# ProProject_MSPM0L1306__2024-08-03.net
KiCad netlist of a schematic drawn in EasyEDA Pro
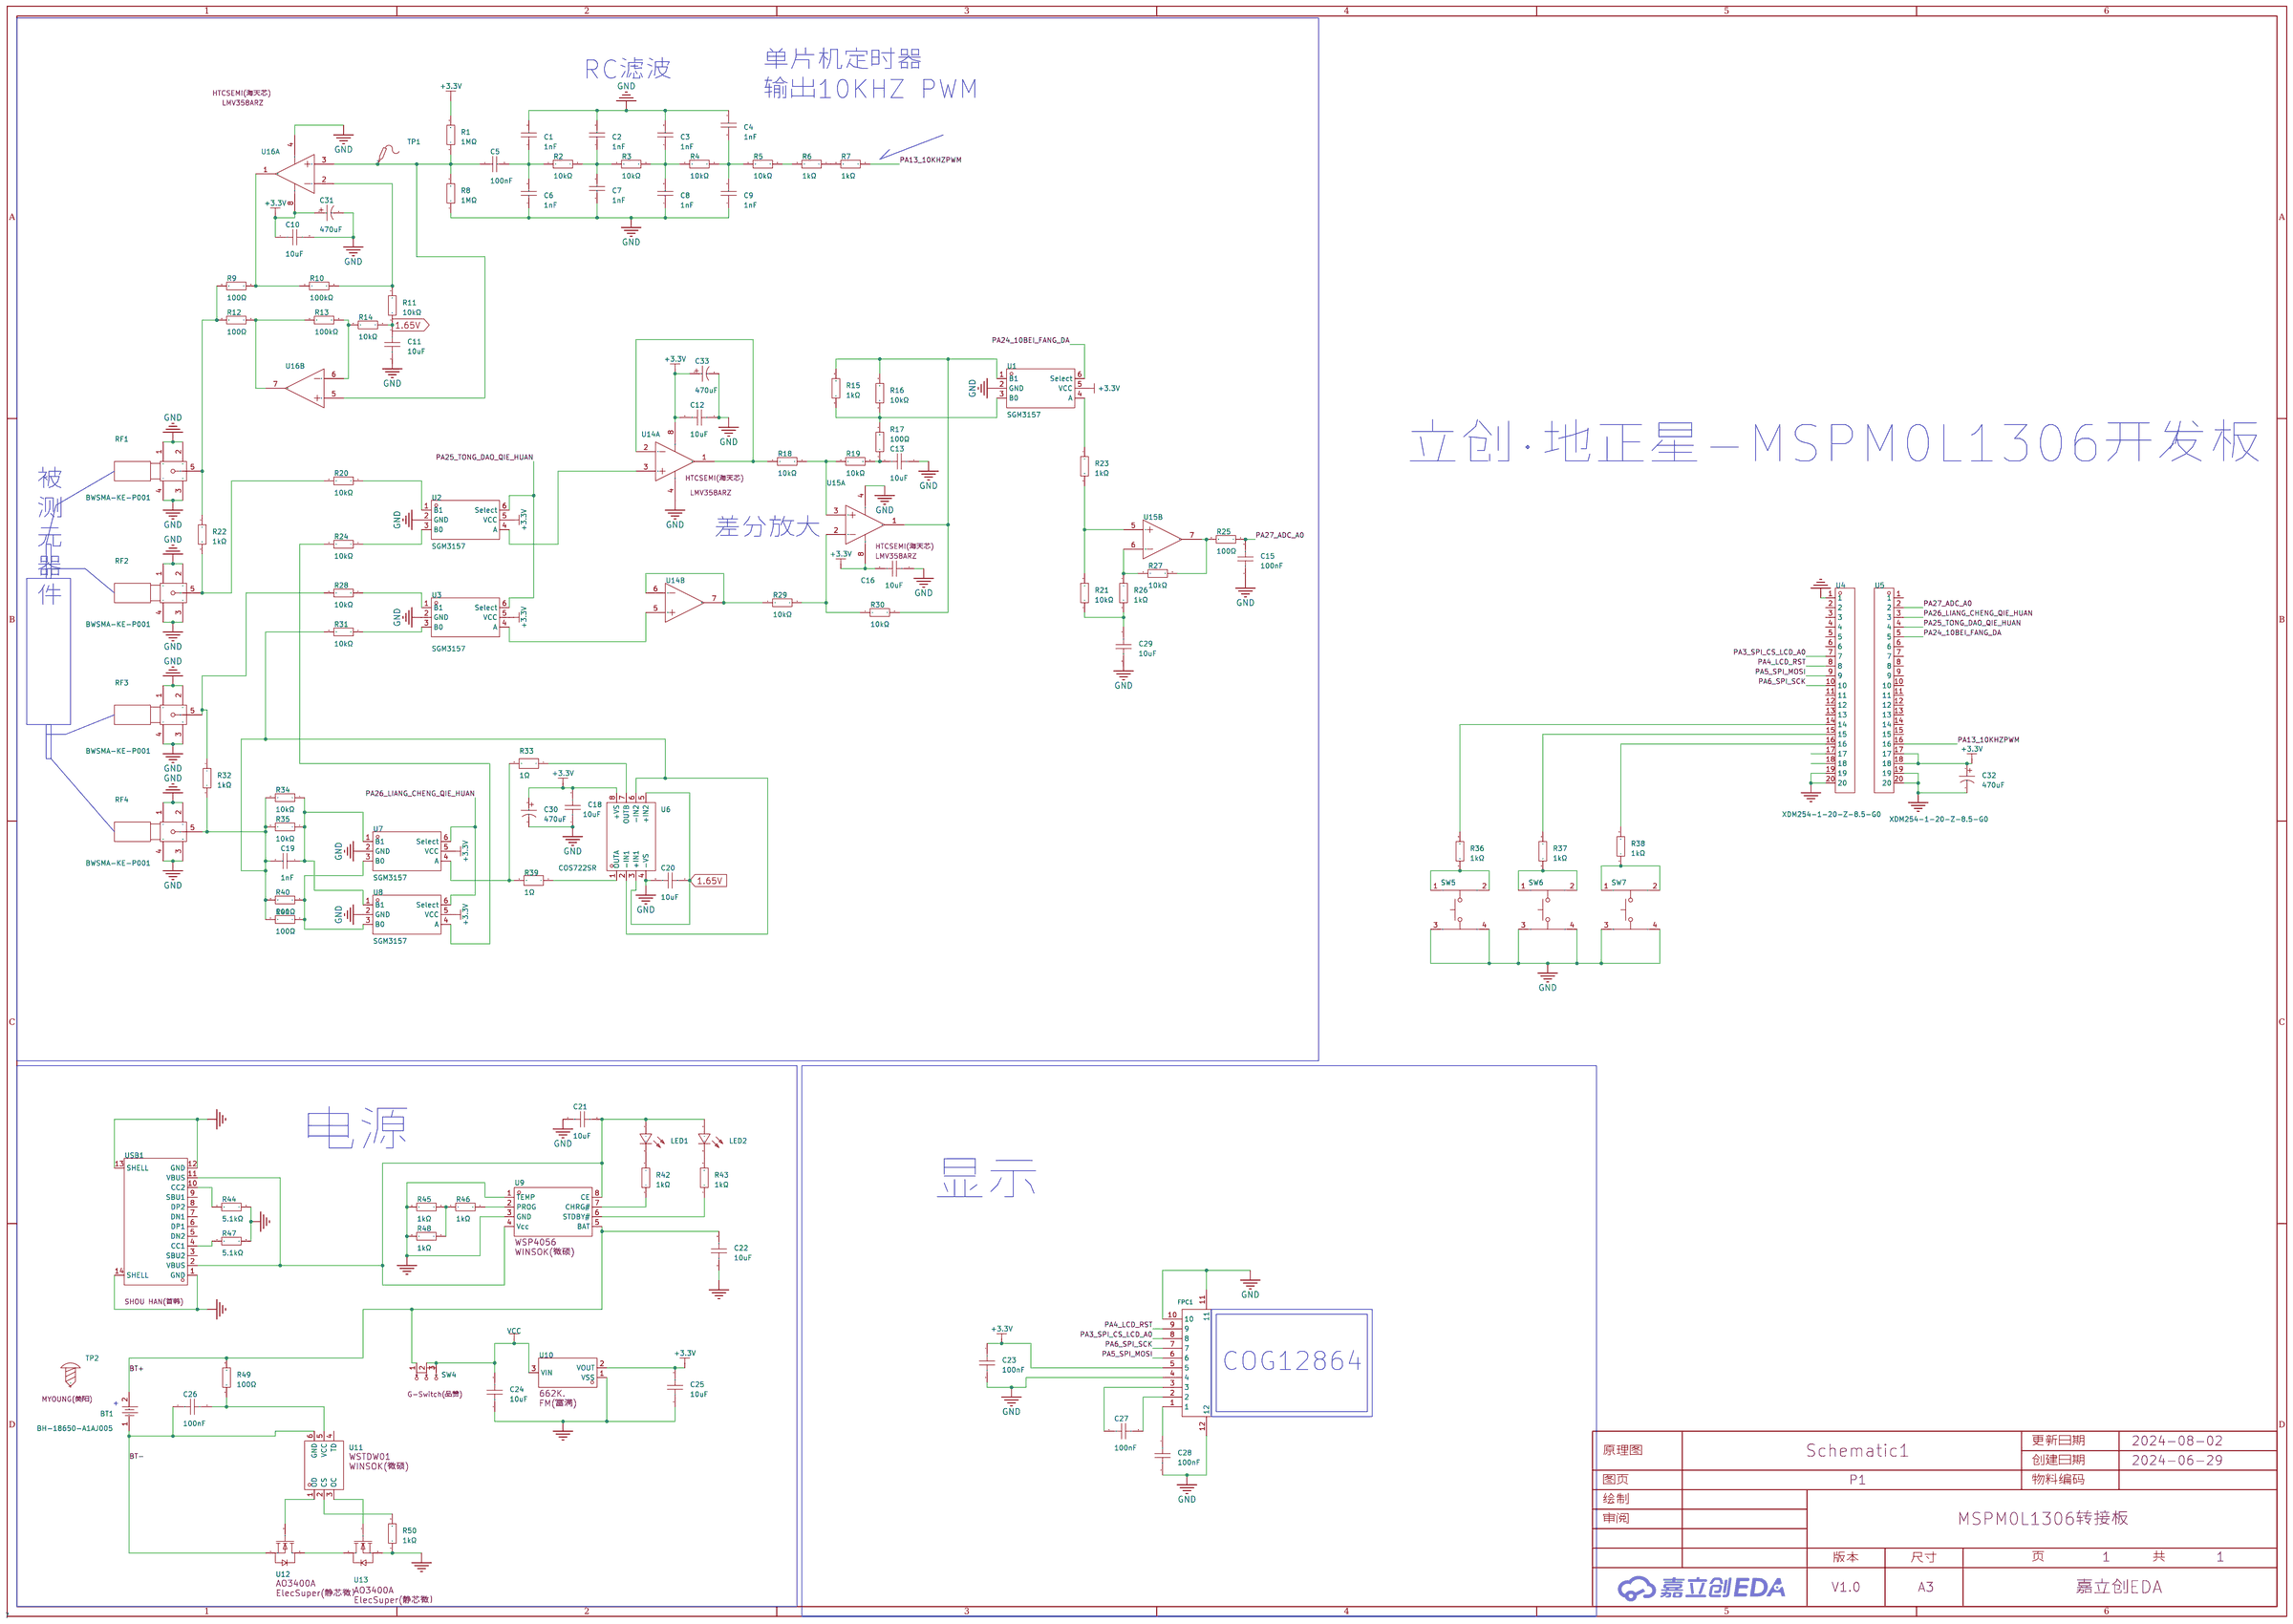
[diagram p0: schematic sheet]

(export (version "E")
  (design (tool "Eeschema 10.0.6"))
  (components
    (comp (ref "BT1")
      (value "BH-18650-A1AJ005")
      (footprint "easyedapro:BAT-TH_BH-18650-A1AJ005")
      (description "连接器类型:电池盒;适用电池规格:CR18650;触点电镀:镍;工作温度范围:-10°C~+100°C;")
      (fields (field (name "Manufacturer") "MYOUNG(美阳)"))
      (libsource (lib "easyedapro") (part "BH-18650-A1AJ005"))
    )
    (comp (ref "C1")
      (value "1nF")
      (footprint "easyedapro:C0603")
      (description "容值:1nF;精度:±5%;额定电压:50V;材质(温度系数):NP0;")
      (fields
        (field (name "Manufacturer Part") "CC0603JRNPO9BN102")
        (field (name "Manufacturer") "YAGEO(国巨)")
      )
      (libsource (lib "easyedapro") (part "CC0603JRNPO9BN102"))
    )
    (comp (ref "C2")
      (value "1nF")
      (footprint "easyedapro:C0603")
      (description "容值:1nF;精度:±5%;额定电压:50V;材质(温度系数):NP0;")
      (fields
        (field (name "Manufacturer Part") "CC0603JRNPO9BN102")
        (field (name "Manufacturer") "YAGEO(国巨)")
      )
      (libsource (lib "easyedapro") (part "CC0603JRNPO9BN102"))
    )
    (comp (ref "C3")
      (value "1nF")
      (footprint "easyedapro:C0603")
      (description "容值:1nF;精度:±5%;额定电压:50V;材质(温度系数):NP0;")
      (fields
        (field (name "Manufacturer Part") "CC0603JRNPO9BN102")
        (field (name "Manufacturer") "YAGEO(国巨)")
      )
      (libsource (lib "easyedapro") (part "CC0603JRNPO9BN102"))
    )
    (comp (ref "C4")
      (value "1nF")
      (footprint "easyedapro:C0603")
      (description "容值:1nF;精度:±5%;额定电压:50V;材质(温度系数):NP0;")
      (fields
        (field (name "Manufacturer Part") "CC0603JRNPO9BN102")
        (field (name "Manufacturer") "YAGEO(国巨)")
      )
      (libsource (lib "easyedapro") (part "CC0603JRNPO9BN102"))
    )
    (comp (ref "C5")
      (value "100nF")
      (footprint "easyedapro:C0603")
      (description "容值:100nF;精度:±10%;额定电压:50V;材质(温度系数):X7R;")
      (fields (field (name "Manufacturer Part") "0603B104K500NT") (field (name "Manufacturer") "FH(风华)"))
      (libsource (lib "easyedapro") (part "0603B104K500NT"))
    )
    (comp (ref "C6")
      (value "1nF")
      (footprint "easyedapro:C0603")
      (description "容值:1nF;精度:±5%;额定电压:50V;材质(温度系数):NP0;")
      (fields
        (field (name "Manufacturer Part") "CC0603JRNPO9BN102")
        (field (name "Manufacturer") "YAGEO(国巨)")
      )
      (libsource (lib "easyedapro") (part "CC0603JRNPO9BN102"))
    )
    (comp (ref "C7")
      (value "1nF")
      (footprint "easyedapro:C0603")
      (description "容值:1nF;精度:±5%;额定电压:50V;材质(温度系数):NP0;")
      (fields
        (field (name "Manufacturer Part") "CC0603JRNPO9BN102")
        (field (name "Manufacturer") "YAGEO(国巨)")
      )
      (libsource (lib "easyedapro") (part "CC0603JRNPO9BN102"))
    )
    (comp (ref "C8")
      (value "1nF")
      (footprint "easyedapro:C0603")
      (description "容值:1nF;精度:±5%;额定电压:50V;材质(温度系数):NP0;")
      (fields
        (field (name "Manufacturer Part") "CC0603JRNPO9BN102")
        (field (name "Manufacturer") "YAGEO(国巨)")
      )
      (libsource (lib "easyedapro") (part "CC0603JRNPO9BN102"))
    )
    (comp (ref "C9")
      (value "1nF")
      (footprint "easyedapro:C0603")
      (description "容值:1nF;精度:±5%;额定电压:50V;材质(温度系数):NP0;")
      (fields
        (field (name "Manufacturer Part") "CC0603JRNPO9BN102")
        (field (name "Manufacturer") "YAGEO(国巨)")
      )
      (libsource (lib "easyedapro") (part "CC0603JRNPO9BN102"))
    )
    (comp (ref "C10")
      (value "10uF")
      (footprint "easyedapro:C0603")
      (description "容值:10uF;精度:±10%;额定电压:10V;材质(温度系数):X5R;")
      (fields
        (field (name "Manufacturer Part") "CL10A106KP8NNNC")
        (field (name "Manufacturer") "SAMSUNG(三星)")
      )
      (libsource (lib "easyedapro") (part "CL10A106KP8NNNC"))
    )
    (comp (ref "C11")
      (value "10uF")
      (footprint "easyedapro:C0603")
      (description "容值:10uF;精度:±10%;额定电压:10V;材质(温度系数):X5R;")
      (fields
        (field (name "Manufacturer Part") "CL10A106KP8NNNC")
        (field (name "Manufacturer") "SAMSUNG(三星)")
      )
      (libsource (lib "easyedapro") (part "CL10A106KP8NNNC"))
    )
    (comp (ref "C12")
      (value "10uF")
      (footprint "easyedapro:C0603")
      (description "容值:10uF;精度:±10%;额定电压:10V;材质(温度系数):X5R;")
      (fields
        (field (name "Manufacturer Part") "CL10A106KP8NNNC")
        (field (name "Manufacturer") "SAMSUNG(三星)")
      )
      (libsource (lib "easyedapro") (part "CL10A106KP8NNNC"))
    )
    (comp (ref "C13")
      (value "10uF")
      (footprint "easyedapro:C0603")
      (description "容值:10uF;精度:±10%;额定电压:10V;材质(温度系数):X5R;")
      (fields
        (field (name "Manufacturer Part") "CL10A106KP8NNNC")
        (field (name "Manufacturer") "SAMSUNG(三星)")
      )
      (libsource (lib "easyedapro") (part "CL10A106KP8NNNC"))
    )
    (comp (ref "C15")
      (value "100nF")
      (footprint "easyedapro:C0603")
      (description "容值:100nF;精度:±10%;额定电压:50V;材质(温度系数):X7R;")
      (fields
        (field (name "Manufacturer Part") "CC0603KRX7R9BB104")
        (field (name "Manufacturer") "YAGEO(国巨)")
      )
      (libsource (lib "easyedapro") (part "CC0603KRX7R9BB104"))
    )
    (comp (ref "C16")
      (value "10uF")
      (footprint "easyedapro:C0603")
      (description "容值:10uF;精度:±10%;额定电压:10V;材质(温度系数):X5R;")
      (fields
        (field (name "Manufacturer Part") "CL10A106KP8NNNC")
        (field (name "Manufacturer") "SAMSUNG(三星)")
      )
      (libsource (lib "easyedapro") (part "CL10A106KP8NNNC"))
    )
    (comp (ref "C18")
      (value "10uF")
      (footprint "easyedapro:C0603")
      (description "容值:10uF;精度:±10%;额定电压:10V;材质(温度系数):X5R;")
      (fields
        (field (name "Manufacturer Part") "CL10A106KP8NNNC")
        (field (name "Manufacturer") "SAMSUNG(三星)")
      )
      (libsource (lib "easyedapro") (part "CL10A106KP8NNNC"))
    )
    (comp (ref "C19")
      (value "1nF")
      (footprint "easyedapro:C0603")
      (description "容值:1nF;精度:±5%;额定电压:50V;材质(温度系数):NP0;")
      (fields
        (field (name "Manufacturer Part") "CC0603JRNPO9BN102")
        (field (name "Manufacturer") "YAGEO(国巨)")
      )
      (libsource (lib "easyedapro") (part "CC0603JRNPO9BN102"))
    )
    (comp (ref "C20")
      (value "10uF")
      (footprint "easyedapro:C0603")
      (description "容值:10uF;精度:±10%;额定电压:10V;材质(温度系数):X5R;")
      (fields
        (field (name "Manufacturer Part") "CL10A106KP8NNNC")
        (field (name "Manufacturer") "SAMSUNG(三星)")
      )
      (libsource (lib "easyedapro") (part "CL10A106KP8NNNC"))
    )
    (comp (ref "C21")
      (value "10uF")
      (footprint "easyedapro:C0603")
      (description "容值:10uF;精度:±10%;额定电压:10V;材质(温度系数):X5R;")
      (fields
        (field (name "Manufacturer Part") "CL10A106KP8NNNC")
        (field (name "Manufacturer") "SAMSUNG(三星)")
      )
      (libsource (lib "easyedapro") (part "CL10A106KP8NNNC"))
    )
    (comp (ref "C22")
      (value "10uF")
      (footprint "easyedapro:C0603")
      (description "容值:10uF;精度:±10%;额定电压:10V;材质(温度系数):X5R;")
      (fields
        (field (name "Manufacturer Part") "CL10A106KP8NNNC")
        (field (name "Manufacturer") "SAMSUNG(三星)")
      )
      (libsource (lib "easyedapro") (part "CL10A106KP8NNNC"))
    )
    (comp (ref "C23")
      (value "100nF")
      (footprint "easyedapro:C0603")
      (description "容值:100nF;精度:±10%;额定电压:50V;材质(温度系数):X7R;")
      (fields
        (field (name "Manufacturer Part") "CC0603KRX7R9BB104")
        (field (name "Manufacturer") "YAGEO(国巨)")
      )
      (libsource (lib "easyedapro") (part "CC0603KRX7R9BB104"))
    )
    (comp (ref "C24")
      (value "10uF")
      (footprint "easyedapro:C0603")
      (description "容值:10uF;精度:±10%;额定电压:10V;材质(温度系数):X5R;")
      (fields
        (field (name "Manufacturer Part") "CL10A106KP8NNNC")
        (field (name "Manufacturer") "SAMSUNG(三星)")
      )
      (libsource (lib "easyedapro") (part "CL10A106KP8NNNC"))
    )
    (comp (ref "C25")
      (value "10uF")
      (footprint "easyedapro:C0603")
      (description "容值:10uF;精度:±10%;额定电压:10V;材质(温度系数):X5R;")
      (fields
        (field (name "Manufacturer Part") "CL10A106KP8NNNC")
        (field (name "Manufacturer") "SAMSUNG(三星)")
      )
      (libsource (lib "easyedapro") (part "CL10A106KP8NNNC"))
    )
    (comp (ref "C26")
      (value "100nF")
      (footprint "easyedapro:C0603")
      (description "容值:100nF;精度:±10%;额定电压:50V;材质(温度系数):X7R;")
      (fields
        (field (name "Manufacturer Part") "CC0603KRX7R9BB104")
        (field (name "Manufacturer") "YAGEO(国巨)")
      )
      (libsource (lib "easyedapro") (part "CC0603KRX7R9BB104"))
    )
    (comp (ref "C27")
      (value "100nF")
      (footprint "easyedapro:C0603")
      (description "容值:100nF;精度:±10%;额定电压:50V;材质(温度系数):X7R;")
      (fields
        (field (name "Manufacturer Part") "CC0603KRX7R9BB104")
        (field (name "Manufacturer") "YAGEO(国巨)")
      )
      (libsource (lib "easyedapro") (part "CC0603KRX7R9BB104"))
    )
    (comp (ref "C28")
      (value "100nF")
      (footprint "easyedapro:C0603")
      (description "容值:100nF;精度:±10%;额定电压:50V;材质(温度系数):X7R;")
      (fields
        (field (name "Manufacturer Part") "CC0603KRX7R9BB104")
        (field (name "Manufacturer") "YAGEO(国巨)")
      )
      (libsource (lib "easyedapro") (part "CC0603KRX7R9BB104"))
    )
    (comp (ref "C29")
      (value "10uF")
      (footprint "easyedapro:C0603")
      (description "容值:10uF;精度:±10%;额定电压:10V;材质(温度系数):X5R;")
      (fields
        (field (name "Manufacturer Part") "CL10A106KP8NNNC")
        (field (name "Manufacturer") "SAMSUNG(三星)")
      )
      (libsource (lib "easyedapro") (part "CL10A106KP8NNNC"))
    )
    (comp (ref "C30")
      (value "470uF")
      (footprint "easyedapro:CAP-TH_BD8.0-P3.50-D0.6-FD")
      (description "容值:470uF;精度:±20%;额定电压:16V;")
      (fields
        (field (name "Manufacturer Part") "KM477M016F12RR0VH2FP0")
        (field (name "Manufacturer") "CX(承兴)")
      )
      (libsource (lib "easyedapro") (part "470uf16v"))
    )
    (comp (ref "C31")
      (value "470uF")
      (footprint "easyedapro:CAP-TH_BD8.0-P3.50-D0.6-FD")
      (description "容值:470uF;精度:±20%;额定电压:16V;")
      (fields
        (field (name "Manufacturer Part") "KM477M016F12RR0VH2FP0")
        (field (name "Manufacturer") "CX(承兴)")
      )
      (libsource (lib "easyedapro") (part "470uf16v"))
    )
    (comp (ref "C32")
      (value "470uF")
      (footprint "easyedapro:CAP-TH_BD8.0-P3.50-D0.6-FD")
      (description "容值:470uF;精度:±20%;额定电压:16V;")
      (fields
        (field (name "Manufacturer Part") "KM477M016F12RR0VH2FP0")
        (field (name "Manufacturer") "CX(承兴)")
      )
      (libsource (lib "easyedapro") (part "470uf16v"))
    )
    (comp (ref "C33")
      (value "470uF")
      (footprint "easyedapro:CAP-TH_BD8.0-P3.50-D0.6-FD")
      (description "容值:470uF;精度:±20%;额定电压:16V;")
      (fields
        (field (name "Manufacturer Part") "KM477M016F12RR0VH2FP0")
        (field (name "Manufacturer") "CX(承兴)")
      )
      (libsource (lib "easyedapro") (part "470uf16v"))
    )
    (comp (ref "FPC1")
      (value "{ManufacturerPart!}")
      (footprint "easyedapro:FPC-SMD_10P-P1.0_FGS-XJ-H2.0")
      (description "间距:1mm;触点数量:10;锁定特性:翻盖式;安装类型:卧贴;触点类型:下接;")
      (fields (field (name "Manufacturer Part") "AFA01-S10FCA-00") (field (name "Manufacturer") "JS(钜硕电子)"))
      (libsource (lib "easyedapro") (part "AFA01-S10FCA-00"))
    )
    (comp (ref "LED1")
      (value "204-10SURD/S530-A3-L")
      (footprint "easyedapro:LED-TH_BD3.0-P2.54-FD")
      (description "发光颜色:红灯;二极管配置:-;主波长:624nm;色温:-;功率:60mW;安装方式:-;")
      (fields (field (name "Manufacturer") "EVERLIGHT(亿光)"))
      (libsource (lib "easyedapro") (part "204-10SURD/S530-A3-L"))
    )
    (comp (ref "LED2")
      (value "204-10SURD/S530-A3-L")
      (footprint "easyedapro:LED-TH_BD3.0-P2.54-FD")
      (description "发光颜色:红灯;二极管配置:-;主波长:624nm;色温:-;功率:60mW;安装方式:-;")
      (fields (field (name "Manufacturer") "EVERLIGHT(亿光)"))
      (libsource (lib "easyedapro") (part "204-10SURD/S530-A3-L"))
    )
    (comp (ref "R1")
      (value "1MΩ")
      (footprint "easyedapro:R0603")
      (description "电阻类型:厚膜电阻;阻值:1MΩ;精度:±1%;功率:100mW;")
      (fields
        (field (name "Manufacturer Part") "0603WAF1004T5E")
        (field (name "Manufacturer") "UNI-ROYAL(厚声)")
      )
      (libsource (lib "easyedapro") (part "0603WAF1004T5E"))
    )
    (comp (ref "R2")
      (value "10kΩ")
      (footprint "easyedapro:R0603")
      (description "电阻类型:厚膜电阻;阻值:10kΩ;精度:±1%;功率:100mW;")
      (fields (field (name "Manufacturer Part") "RC0603FR-0710KL") (field (name "Manufacturer") "YAGEO(国巨)"))
      (libsource (lib "easyedapro") (part "RC0603FR-0710KL"))
    )
    (comp (ref "R3")
      (value "10kΩ")
      (footprint "easyedapro:R0603")
      (description "电阻类型:厚膜电阻;阻值:10kΩ;精度:±1%;功率:100mW;")
      (fields (field (name "Manufacturer Part") "RC0603FR-0710KL") (field (name "Manufacturer") "YAGEO(国巨)"))
      (libsource (lib "easyedapro") (part "RC0603FR-0710KL"))
    )
    (comp (ref "R4")
      (value "10kΩ")
      (footprint "easyedapro:R0603")
      (description "电阻类型:厚膜电阻;阻值:10kΩ;精度:±1%;功率:100mW;")
      (fields (field (name "Manufacturer Part") "RC0603FR-0710KL") (field (name "Manufacturer") "YAGEO(国巨)"))
      (libsource (lib "easyedapro") (part "RC0603FR-0710KL"))
    )
    (comp (ref "R5")
      (value "10kΩ")
      (footprint "easyedapro:R0603")
      (description "电阻类型:厚膜电阻;阻值:10kΩ;精度:±1%;功率:100mW;")
      (fields (field (name "Manufacturer Part") "RC0603FR-0710KL") (field (name "Manufacturer") "YAGEO(国巨)"))
      (libsource (lib "easyedapro") (part "RC0603FR-0710KL"))
    )
    (comp (ref "R6")
      (value "1kΩ")
      (footprint "easyedapro:R0603")
      (description "电阻类型:厚膜电阻;阻值:1kΩ;精度:±1%;功率:100mW;")
      (fields (field (name "Manufacturer Part") "RC0603FR-071KL") (field (name "Manufacturer") "YAGEO(国巨)"))
      (libsource (lib "easyedapro") (part "RC0603FR-071KL"))
    )
    (comp (ref "R7")
      (value "1kΩ")
      (footprint "easyedapro:R0603")
      (description "电阻类型:厚膜电阻;阻值:1kΩ;精度:±1%;功率:100mW;")
      (fields (field (name "Manufacturer Part") "RC0603FR-071KL") (field (name "Manufacturer") "YAGEO(国巨)"))
      (libsource (lib "easyedapro") (part "RC0603FR-071KL"))
    )
    (comp (ref "R8")
      (value "1MΩ")
      (footprint "easyedapro:R0603")
      (description "电阻类型:厚膜电阻;阻值:1MΩ;精度:±1%;功率:100mW;")
      (fields
        (field (name "Manufacturer Part") "0603WAF1004T5E")
        (field (name "Manufacturer") "UNI-ROYAL(厚声)")
      )
      (libsource (lib "easyedapro") (part "0603WAF1004T5E"))
    )
    (comp (ref "R9")
      (value "100Ω")
      (footprint "easyedapro:R0603")
      (description "电阻类型:厚膜电阻;阻值:100Ω;精度:±1%;功率:100mW;")
      (fields (field (name "Manufacturer Part") "RC0603FR-07100RL") (field (name "Manufacturer") "YAGEO(国巨)"))
      (libsource (lib "easyedapro") (part "RC0603FR-07100RL"))
    )
    (comp (ref "R10")
      (value "100kΩ")
      (footprint "easyedapro:R0603")
      (description "电阻类型:厚膜电阻;阻值:100kΩ;精度:±1%;功率:100mW;")
      (fields (field (name "Manufacturer Part") "RC0603FR-07100KL") (field (name "Manufacturer") "YAGEO(国巨)"))
      (libsource (lib "easyedapro") (part "RC0603FR-07100KL"))
    )
    (comp (ref "R11")
      (value "10kΩ")
      (footprint "easyedapro:R0603")
      (description "电阻类型:厚膜电阻;阻值:10kΩ;精度:±1%;功率:100mW;")
      (fields (field (name "Manufacturer Part") "RC0603FR-0710KL") (field (name "Manufacturer") "YAGEO(国巨)"))
      (libsource (lib "easyedapro") (part "RC0603FR-0710KL"))
    )
    (comp (ref "R12")
      (value "100Ω")
      (footprint "easyedapro:R0603")
      (description "电阻类型:厚膜电阻;阻值:100Ω;精度:±1%;功率:100mW;")
      (fields (field (name "Manufacturer Part") "RC0603FR-07100RL") (field (name "Manufacturer") "YAGEO(国巨)"))
      (libsource (lib "easyedapro") (part "RC0603FR-07100RL"))
    )
    (comp (ref "R13")
      (value "100kΩ")
      (footprint "easyedapro:R0603")
      (description "电阻类型:厚膜电阻;阻值:100kΩ;精度:±1%;功率:100mW;")
      (fields (field (name "Manufacturer Part") "RC0603FR-07100KL") (field (name "Manufacturer") "YAGEO(国巨)"))
      (libsource (lib "easyedapro") (part "RC0603FR-07100KL"))
    )
    (comp (ref "R14")
      (value "10kΩ")
      (footprint "easyedapro:R0603")
      (description "电阻类型:厚膜电阻;阻值:10kΩ;精度:±1%;功率:100mW;")
      (fields (field (name "Manufacturer Part") "RC0603FR-0710KL") (field (name "Manufacturer") "YAGEO(国巨)"))
      (libsource (lib "easyedapro") (part "RC0603FR-0710KL"))
    )
    (comp (ref "R15")
      (value "1kΩ")
      (footprint "easyedapro:R0603")
      (description "电阻类型:厚膜电阻;阻值:1kΩ;精度:±1%;功率:100mW;")
      (fields (field (name "Manufacturer Part") "RC0603FR-071KL") (field (name "Manufacturer") "YAGEO(国巨)"))
      (libsource (lib "easyedapro") (part "RC0603FR-071KL"))
    )
    (comp (ref "R16")
      (value "10kΩ")
      (footprint "easyedapro:R0603")
      (description "电阻类型:厚膜电阻;阻值:10kΩ;精度:±1%;功率:100mW;")
      (fields (field (name "Manufacturer Part") "RC0603FR-0710KL") (field (name "Manufacturer") "YAGEO(国巨)"))
      (libsource (lib "easyedapro") (part "RC0603FR-0710KL"))
    )
    (comp (ref "R17")
      (value "100Ω")
      (footprint "easyedapro:R0603")
      (description "电阻类型:厚膜电阻;阻值:100Ω;精度:±1%;功率:100mW;")
      (fields (field (name "Manufacturer Part") "RC0603FR-07100RL") (field (name "Manufacturer") "YAGEO(国巨)"))
      (libsource (lib "easyedapro") (part "RC0603FR-07100RL"))
    )
    (comp (ref "R18")
      (value "10kΩ")
      (footprint "easyedapro:R0603")
      (description "电阻类型:厚膜电阻;阻值:10kΩ;精度:±1%;功率:100mW;")
      (fields (field (name "Manufacturer Part") "RC0603FR-0710KL") (field (name "Manufacturer") "YAGEO(国巨)"))
      (libsource (lib "easyedapro") (part "RC0603FR-0710KL"))
    )
    (comp (ref "R19")
      (value "10kΩ")
      (footprint "easyedapro:R0603")
      (description "电阻类型:厚膜电阻;阻值:10kΩ;精度:±1%;功率:100mW;")
      (fields (field (name "Manufacturer Part") "RC0603FR-0710KL") (field (name "Manufacturer") "YAGEO(国巨)"))
      (libsource (lib "easyedapro") (part "RC0603FR-0710KL"))
    )
    (comp (ref "R20")
      (value "10kΩ")
      (footprint "easyedapro:R0603")
      (description "电阻类型:厚膜电阻;阻值:10kΩ;精度:±1%;功率:100mW;")
      (fields (field (name "Manufacturer Part") "RC0603FR-0710KL") (field (name "Manufacturer") "YAGEO(国巨)"))
      (libsource (lib "easyedapro") (part "RC0603FR-0710KL"))
    )
    (comp (ref "R21")
      (value "10kΩ")
      (footprint "easyedapro:R0603")
      (description "电阻类型:厚膜电阻;阻值:10kΩ;精度:±1%;功率:100mW;")
      (fields (field (name "Manufacturer Part") "RC0603FR-0710KL") (field (name "Manufacturer") "YAGEO(国巨)"))
      (libsource (lib "easyedapro") (part "RC0603FR-0710KL"))
    )
    (comp (ref "R22")
      (value "1kΩ")
      (footprint "easyedapro:R0603")
      (description "电阻类型:厚膜电阻;阻值:1kΩ;精度:±1%;功率:100mW;")
      (fields (field (name "Manufacturer Part") "RC0603FR-071KL") (field (name "Manufacturer") "YAGEO(国巨)"))
      (libsource (lib "easyedapro") (part "RC0603FR-071KL"))
    )
    (comp (ref "R23")
      (value "1kΩ")
      (footprint "easyedapro:R0603")
      (description "电阻类型:厚膜电阻;阻值:1kΩ;精度:±1%;功率:100mW;")
      (fields (field (name "Manufacturer Part") "RC0603FR-071KL") (field (name "Manufacturer") "YAGEO(国巨)"))
      (libsource (lib "easyedapro") (part "RC0603FR-071KL"))
    )
    (comp (ref "R24")
      (value "10kΩ")
      (footprint "easyedapro:R0603")
      (description "电阻类型:厚膜电阻;阻值:10kΩ;精度:±1%;功率:100mW;")
      (fields (field (name "Manufacturer Part") "RC0603FR-0710KL") (field (name "Manufacturer") "YAGEO(国巨)"))
      (libsource (lib "easyedapro") (part "RC0603FR-0710KL"))
    )
    (comp (ref "R25")
      (value "100Ω")
      (footprint "easyedapro:R0603")
      (description "电阻类型:厚膜电阻;阻值:100Ω;精度:±1%;功率:100mW;")
      (fields (field (name "Manufacturer Part") "RC0603FR-07100RL") (field (name "Manufacturer") "YAGEO(国巨)"))
      (libsource (lib "easyedapro") (part "RC0603FR-07100RL"))
    )
    (comp (ref "R26")
      (value "1kΩ")
      (footprint "easyedapro:R0603")
      (description "电阻类型:厚膜电阻;阻值:1kΩ;精度:±1%;功率:100mW;")
      (fields (field (name "Manufacturer Part") "RC0603FR-071KL") (field (name "Manufacturer") "YAGEO(国巨)"))
      (libsource (lib "easyedapro") (part "RC0603FR-071KL"))
    )
    (comp (ref "R27")
      (value "10kΩ")
      (footprint "easyedapro:R0603")
      (description "电阻类型:厚膜电阻;阻值:10kΩ;精度:±1%;功率:100mW;")
      (fields (field (name "Manufacturer Part") "RC0603FR-0710KL") (field (name "Manufacturer") "YAGEO(国巨)"))
      (libsource (lib "easyedapro") (part "RC0603FR-0710KL"))
    )
    (comp (ref "R28")
      (value "10kΩ")
      (footprint "easyedapro:R0603")
      (description "电阻类型:厚膜电阻;阻值:10kΩ;精度:±1%;功率:100mW;")
      (fields (field (name "Manufacturer Part") "RC0603FR-0710KL") (field (name "Manufacturer") "YAGEO(国巨)"))
      (libsource (lib "easyedapro") (part "RC0603FR-0710KL"))
    )
    (comp (ref "R29")
      (value "10kΩ")
      (footprint "easyedapro:R0603")
      (description "电阻类型:厚膜电阻;阻值:10kΩ;精度:±1%;功率:100mW;")
      (fields (field (name "Manufacturer Part") "RC0603FR-0710KL") (field (name "Manufacturer") "YAGEO(国巨)"))
      (libsource (lib "easyedapro") (part "RC0603FR-0710KL"))
    )
    (comp (ref "R30")
      (value "10kΩ")
      (footprint "easyedapro:R0603")
      (description "电阻类型:厚膜电阻;阻值:10kΩ;精度:±1%;功率:100mW;")
      (fields (field (name "Manufacturer Part") "RC0603FR-0710KL") (field (name "Manufacturer") "YAGEO(国巨)"))
      (libsource (lib "easyedapro") (part "RC0603FR-0710KL"))
    )
    (comp (ref "R31")
      (value "10kΩ")
      (footprint "easyedapro:R0603")
      (description "电阻类型:厚膜电阻;阻值:10kΩ;精度:±1%;功率:100mW;")
      (fields (field (name "Manufacturer Part") "RC0603FR-0710KL") (field (name "Manufacturer") "YAGEO(国巨)"))
      (libsource (lib "easyedapro") (part "RC0603FR-0710KL"))
    )
    (comp (ref "R32")
      (value "1kΩ")
      (footprint "easyedapro:R0603")
      (description "电阻类型:厚膜电阻;阻值:1kΩ;精度:±1%;功率:100mW;")
      (fields (field (name "Manufacturer Part") "RC0603FR-071KL") (field (name "Manufacturer") "YAGEO(国巨)"))
      (libsource (lib "easyedapro") (part "RC0603FR-071KL"))
    )
    (comp (ref "R33")
      (value "1Ω")
      (footprint "easyedapro:R0603")
      (description "阻值:1Ω;精度:±1%;")
      (fields (field (name "Manufacturer Part") "SCR0603F1R") (field (name "Manufacturer") "VO(翔胜)"))
      (libsource (lib "easyedapro") (part "SCR0603F1R"))
    )
    (comp (ref "R34")
      (value "10kΩ")
      (footprint "easyedapro:R0603")
      (description "电阻类型:厚膜电阻;阻值:10kΩ;精度:±1%;功率:100mW;")
      (fields (field (name "Manufacturer Part") "RC0603FR-0710KL") (field (name "Manufacturer") "YAGEO(国巨)"))
      (libsource (lib "easyedapro") (part "RC0603FR-0710KL"))
    )
    (comp (ref "R35")
      (value "10kΩ")
      (footprint "easyedapro:R0603")
      (description "电阻类型:厚膜电阻;阻值:10kΩ;精度:±1%;功率:100mW;")
      (fields (field (name "Manufacturer Part") "RC0603FR-0710KL") (field (name "Manufacturer") "YAGEO(国巨)"))
      (libsource (lib "easyedapro") (part "RC0603FR-0710KL"))
    )
    (comp (ref "R36")
      (value "1kΩ")
      (footprint "easyedapro:R0603")
      (description "电阻类型:厚膜电阻;阻值:1kΩ;精度:±1%;功率:100mW;")
      (fields (field (name "Manufacturer Part") "RC0603FR-071KL") (field (name "Manufacturer") "YAGEO(国巨)"))
      (libsource (lib "easyedapro") (part "RC0603FR-071KL"))
    )
    (comp (ref "R37")
      (value "1kΩ")
      (footprint "easyedapro:R0603")
      (description "电阻类型:厚膜电阻;阻值:1kΩ;精度:±1%;功率:100mW;")
      (fields (field (name "Manufacturer Part") "RC0603FR-071KL") (field (name "Manufacturer") "YAGEO(国巨)"))
      (libsource (lib "easyedapro") (part "RC0603FR-071KL"))
    )
    (comp (ref "R38")
      (value "1kΩ")
      (footprint "easyedapro:R0603")
      (description "电阻类型:厚膜电阻;阻值:1kΩ;精度:±1%;功率:100mW;")
      (fields (field (name "Manufacturer Part") "RC0603FR-071KL") (field (name "Manufacturer") "YAGEO(国巨)"))
      (libsource (lib "easyedapro") (part "RC0603FR-071KL"))
    )
    (comp (ref "R39")
      (value "1Ω")
      (footprint "easyedapro:R0603")
      (description "阻值:1Ω;精度:±1%;")
      (fields (field (name "Manufacturer Part") "SCR0603F1R") (field (name "Manufacturer") "VO(翔胜)"))
      (libsource (lib "easyedapro") (part "SCR0603F1R"))
    )
    (comp (ref "R40")
      (value "100Ω")
      (footprint "easyedapro:R0603")
      (description "电阻类型:厚膜电阻;阻值:100Ω;精度:±1%;功率:100mW;")
      (fields (field (name "Manufacturer Part") "RC0603FR-07100RL") (field (name "Manufacturer") "YAGEO(国巨)"))
      (libsource (lib "easyedapro") (part "RC0603FR-07100RL"))
    )
    (comp (ref "R41")
      (value "100Ω")
      (footprint "easyedapro:R0603")
      (description "电阻类型:厚膜电阻;阻值:100Ω;精度:±1%;功率:100mW;")
      (fields (field (name "Manufacturer Part") "RC0603FR-07100RL") (field (name "Manufacturer") "YAGEO(国巨)"))
      (libsource (lib "easyedapro") (part "RC0603FR-07100RL"))
    )
    (comp (ref "R42")
      (value "1kΩ")
      (footprint "easyedapro:R0603")
      (description "电阻类型:厚膜电阻;阻值:1kΩ;精度:±1%;功率:100mW;")
      (fields (field (name "Manufacturer Part") "RC0603FR-071KL") (field (name "Manufacturer") "YAGEO(国巨)"))
      (libsource (lib "easyedapro") (part "RC0603FR-071KL"))
    )
    (comp (ref "R43")
      (value "1kΩ")
      (footprint "easyedapro:R0603")
      (description "电阻类型:厚膜电阻;阻值:1kΩ;精度:±1%;功率:100mW;")
      (fields (field (name "Manufacturer Part") "RC0603FR-071KL") (field (name "Manufacturer") "YAGEO(国巨)"))
      (libsource (lib "easyedapro") (part "RC0603FR-071KL"))
    )
    (comp (ref "R44")
      (value "5.1kΩ")
      (footprint "easyedapro:R0603")
      (description "电阻类型:厚膜电阻;阻值:10kΩ;精度:±1%;功率:100mW;")
      (fields (field (name "Manufacturer Part") "RC0603FR-0710KL") (field (name "Manufacturer") "YAGEO(国巨)"))
      (libsource (lib "easyedapro") (part "RC0603FR-0710KL"))
    )
    (comp (ref "R45")
      (value "1kΩ")
      (footprint "easyedapro:R0603")
      (description "电阻类型:厚膜电阻;阻值:1kΩ;精度:±1%;功率:100mW;")
      (fields (field (name "Manufacturer Part") "RC0603FR-071KL") (field (name "Manufacturer") "YAGEO(国巨)"))
      (libsource (lib "easyedapro") (part "RC0603FR-071KL"))
    )
    (comp (ref "R46")
      (value "1kΩ")
      (footprint "easyedapro:R0603")
      (description "电阻类型:厚膜电阻;阻值:1kΩ;精度:±1%;功率:100mW;")
      (fields (field (name "Manufacturer Part") "RC0603FR-071KL") (field (name "Manufacturer") "YAGEO(国巨)"))
      (libsource (lib "easyedapro") (part "RC0603FR-071KL"))
    )
    (comp (ref "R47")
      (value "5.1kΩ")
      (footprint "easyedapro:R0603")
      (description "电阻类型:厚膜电阻;阻值:10kΩ;精度:±1%;功率:100mW;")
      (fields (field (name "Manufacturer Part") "RC0603FR-0710KL") (field (name "Manufacturer") "YAGEO(国巨)"))
      (libsource (lib "easyedapro") (part "RC0603FR-0710KL"))
    )
    (comp (ref "R48")
      (value "1kΩ")
      (footprint "easyedapro:R0603")
      (description "电阻类型:厚膜电阻;阻值:1kΩ;精度:±1%;功率:100mW;")
      (fields (field (name "Manufacturer Part") "RC0603FR-071KL") (field (name "Manufacturer") "YAGEO(国巨)"))
      (libsource (lib "easyedapro") (part "RC0603FR-071KL"))
    )
    (comp (ref "R49")
      (value "100Ω")
      (footprint "easyedapro:R0603")
      (description "电阻类型:厚膜电阻;阻值:100Ω;精度:±1%;功率:100mW;")
      (fields (field (name "Manufacturer Part") "RC0603FR-07100RL") (field (name "Manufacturer") "YAGEO(国巨)"))
      (libsource (lib "easyedapro") (part "RC0603FR-07100RL"))
    )
    (comp (ref "R50")
      (value "1kΩ")
      (footprint "easyedapro:R0603")
      (description "电阻类型:厚膜电阻;阻值:1kΩ;精度:±1%;功率:100mW;")
      (fields (field (name "Manufacturer Part") "RC0603FR-071KL") (field (name "Manufacturer") "YAGEO(国巨)"))
      (libsource (lib "easyedapro") (part "RC0603FR-071KL"))
    )
    (comp (ref "RF1")
      (value "BWSMA-KE-P001")
      (footprint "easyedapro:SMA-SMD_BWSMA-KE-P001")
      (description "连接器类型:板端;接口类型:内孔;端口数量:1;接口直径:5.2mm;接口长度/高度:-;频率-最大值:-;射频系列:SMA;阻抗:50Ω;样式:偏脚;工作温度范围:-;")
      (fields (field (name "Manufacturer") "BAT WIRELESS(蝙蝠无线)"))
      (libsource (lib "easyedapro") (part "BWSMA-KE-P001"))
    )
    (comp (ref "RF2")
      (value "BWSMA-KE-P001")
      (footprint "easyedapro:SMA-SMD_BWSMA-KE-P001")
      (description "连接器类型:板端;接口类型:内孔;端口数量:1;接口直径:5.2mm;接口长度/高度:-;频率-最大值:-;射频系列:SMA;阻抗:50Ω;样式:偏脚;工作温度范围:-;")
      (fields (field (name "Manufacturer") "BAT WIRELESS(蝙蝠无线)"))
      (libsource (lib "easyedapro") (part "BWSMA-KE-P001"))
    )
    (comp (ref "RF3")
      (value "BWSMA-KE-P001")
      (footprint "easyedapro:SMA-SMD_BWSMA-KE-P001")
      (description "连接器类型:板端;接口类型:内孔;端口数量:1;接口直径:5.2mm;接口长度/高度:-;频率-最大值:-;射频系列:SMA;阻抗:50Ω;样式:偏脚;工作温度范围:-;")
      (fields (field (name "Manufacturer") "BAT WIRELESS(蝙蝠无线)"))
      (libsource (lib "easyedapro") (part "BWSMA-KE-P001"))
    )
    (comp (ref "RF4")
      (value "BWSMA-KE-P001")
      (footprint "easyedapro:SMA-SMD_BWSMA-KE-P001")
      (description "连接器类型:板端;接口类型:内孔;端口数量:1;接口直径:5.2mm;接口长度/高度:-;频率-最大值:-;射频系列:SMA;阻抗:50Ω;样式:偏脚;工作温度范围:-;")
      (fields (field (name "Manufacturer") "BAT WIRELESS(蝙蝠无线)"))
      (libsource (lib "easyedapro") (part "BWSMA-KE-P001"))
    )
    (comp (ref "SW4")
      (value "SS-12F20-G070")
      (footprint "easyedapro:SW-TH_G-SWITCH_SS-12F20-G070")
      (description "额定电流(DC):500mA;额定电压(DC):250V;电路结构:单刀双掷;安装方式:直插;机械寿命:-;开关颜色:黑色;")
      (fields (field (name "Manufacturer") "G-Switch(品赞)"))
      (libsource (lib "easyedapro") (part "SS-12F20-G070"))
    )
    (comp (ref "SW5")
      (value "{ManufacturerPart!}")
      (footprint "easyedapro:SW-TH_4P-L6.0-W6.0-P3.90-LS6.5")
      (description "触点电流:50mA;额定电压(DC):12V;额定功率:0.6W;绝缘电阻:100MΩ;电路结构:单刀单掷;安装方式:直插;带灯:无;作用力:250gf@±50gf;机械寿命:7万次;带支架:否;")
      (fields
        (field (name "Manufacturer Part") "1TS005A-2500-5001")
        (field (name "Manufacturer") "HYP(鸿源精密)")
      )
      (libsource (lib "easyedapro") (part "1TS005A-2500-5001"))
    )
    (comp (ref "SW6")
      (value "{ManufacturerPart!}")
      (footprint "easyedapro:SW-TH_4P-L6.0-W6.0-P3.90-LS6.5")
      (description "触点电流:50mA;额定电压(DC):12V;额定功率:0.6W;绝缘电阻:100MΩ;电路结构:单刀单掷;安装方式:直插;带灯:无;作用力:250gf@±50gf;机械寿命:7万次;带支架:否;")
      (fields
        (field (name "Manufacturer Part") "1TS005A-2500-5001")
        (field (name "Manufacturer") "HYP(鸿源精密)")
      )
      (libsource (lib "easyedapro") (part "1TS005A-2500-5001"))
    )
    (comp (ref "SW7")
      (value "{ManufacturerPart!}")
      (footprint "easyedapro:SW-TH_4P-L6.0-W6.0-P3.90-LS6.5")
      (description "触点电流:50mA;额定电压(DC):12V;额定功率:0.6W;绝缘电阻:100MΩ;电路结构:单刀单掷;安装方式:直插;带灯:无;作用力:250gf@±50gf;机械寿命:7万次;带支架:否;")
      (fields
        (field (name "Manufacturer Part") "1TS005A-2500-5001")
        (field (name "Manufacturer") "HYP(鸿源精密)")
      )
      (libsource (lib "easyedapro") (part "1TS005A-2500-5001"))
    )
    (comp (ref "TP1")
      (value "~")
      (footprint "easyedapro:Test-Point-0.5mm")
      (description "Test Point 测试点")
      (libsource (lib "easyedapro") (part "Test-Point"))
    )
    (comp (ref "TP2") (value "~") (footprint "easyedapro:M3螺丝") (libsource (lib "easyedapro") (part "螺丝孔")))
    (comp (ref "U1")
      (value "SGM3157")
      (footprint "easyedapro:SC-70-6_L2.2-W1.3-P0.65-LS2.1-BL")
      (description "开关电路:-;")
      (fields (field (name "Manufacturer") "UMW(广东友台半导体)"))
      (libsource (lib "easyedapro") (part "SGM3157"))
    )
    (comp (ref "U2")
      (value "SGM3157")
      (footprint "easyedapro:SC-70-6_L2.2-W1.3-P0.65-LS2.1-BL")
      (description "开关电路:-;")
      (fields (field (name "Manufacturer") "UMW(广东友台半导体)"))
      (libsource (lib "easyedapro") (part "SGM3157"))
    )
    (comp (ref "U3")
      (value "SGM3157")
      (footprint "easyedapro:SC-70-6_L2.2-W1.3-P0.65-LS2.1-BL")
      (description "开关电路:-;")
      (fields (field (name "Manufacturer") "UMW(广东友台半导体)"))
      (libsource (lib "easyedapro") (part "SGM3157"))
    )
    (comp (ref "U4")
      (value "XDM254-1-20-Z-8.5-G0")
      (footprint "easyedapro:HDR-TH_20P-P2.54-V-F-2")
      (description "插孔结构:1x20P;间距:2.54mm;圆孔/方孔:方孔;安装类型:直插;排数:单排;总孔位数:20P;额定电流:3A;插孔方向:顶部;塑高:8.5mm;工作温度范围:-40°C~+105°C;")
      (fields (field (name "Manufacturer") "XUNDA(讯答)"))
      (libsource (lib "easyedapro") (part "XDM254-1-20-Z-8.5-G0"))
    )
    (comp (ref "U5")
      (value "XDM254-1-20-Z-8.5-G0")
      (footprint "easyedapro:HDR-TH_20P-P2.54-V-F-2")
      (description "插孔结构:1x20P;间距:2.54mm;圆孔/方孔:方孔;安装类型:直插;排数:单排;总孔位数:20P;额定电流:3A;插孔方向:顶部;塑高:8.5mm;工作温度范围:-40°C~+105°C;")
      (fields (field (name "Manufacturer") "XUNDA(讯答)"))
      (libsource (lib "easyedapro") (part "XDM254-1-20-Z-8.5-G0"))
    )
    (comp (ref "U6")
      (value "COS722SR")
      (footprint "easyedapro:SOIC-8_L4.9-W3.9-P1.27-LS6.0-BL")
      (description "放大器数:双路;增益带宽积(GBP):10MHz;输入失调电压(Vos):5mV;压摆率(SR):7.5V/us;")
      (fields (field (name "Manufacturer") "COSINE(科山芯创)"))
      (libsource (lib "easyedapro") (part "COS722SR"))
    )
    (comp (ref "U7")
      (value "SGM3157")
      (footprint "easyedapro:SC-70-6_L2.2-W1.3-P0.65-LS2.1-BL")
      (description "开关电路:-;")
      (fields (field (name "Manufacturer") "UMW(广东友台半导体)"))
      (libsource (lib "easyedapro") (part "SGM3157"))
    )
    (comp (ref "U8")
      (value "SGM3157")
      (footprint "easyedapro:SC-70-6_L2.2-W1.3-P0.65-LS2.1-BL")
      (description "开关电路:-;")
      (fields (field (name "Manufacturer") "UMW(广东友台半导体)"))
      (libsource (lib "easyedapro") (part "SGM3157"))
    )
    (comp (ref "U9")
      (value "WSP4056")
      (footprint "easyedapro:SOP-8_L5.1-W3.9-P1.27-LS6.0-BL")
      (fields (field (name "Manufacturer Part") "WSP4056") (field (name "Manufacturer") "WINSOK(微硕)"))
      (libsource (lib "easyedapro") (part "WSP4056"))
    )
    (comp (ref "U10")
      (value "662K.")
      (footprint "easyedapro:SOT-23-3_L2.9-W1.3-P1.90-LS2.4-BR")
      (description "输出类型:-;")
      (fields (field (name "Manufacturer Part") "662K.") (field (name "Manufacturer") "FM(富满)"))
      (libsource (lib "easyedapro") (part "662K."))
    )
    (comp (ref "U11")
      (value "WSTDW01")
      (footprint "easyedapro:SOT-23-6_L2.9-W1.6-P0.95-LS2.8-BR")
      (description "充电电池的类型:-;电池单元组数:-;最大充电电流:-;充满的电池组电压:-;最大供应电压:-;")
      (fields (field (name "Manufacturer Part") "WSTDW01") (field (name "Manufacturer") "WINSOK(微硕)"))
      (libsource (lib "easyedapro") (part "WSTDW01"))
    )
    (comp (ref "U12")
      (value "AO3400A")
      (footprint "easyedapro:SOT-23-3_L3.0-W1.6-P1.90-LS2.8-BR")
      (description "类型:N沟道;漏源电压(Vdss):30V;连续漏极电流(Id):6A;功率(Pd):1.4W;导通电阻(RDS(on)@Vgs,Id):19mΩ@10V,6.0A;")
      (fields (field (name "Manufacturer Part") "AO3400A") (field (name "Manufacturer") "ElecSuper(静芯微）"))
      (libsource (lib "easyedapro") (part "AO3400A_C5224194"))
    )
    (comp (ref "U13")
      (value "AO3400A")
      (footprint "easyedapro:SOT-23-3_L3.0-W1.6-P1.90-LS2.8-BR")
      (description "类型:N沟道;漏源电压(Vdss):30V;连续漏极电流(Id):6A;功率(Pd):1.4W;导通电阻(RDS(on)@Vgs,Id):19mΩ@10V,6.0A;")
      (fields (field (name "Manufacturer Part") "AO3400A") (field (name "Manufacturer") "ElecSuper(静芯微）"))
      (libsource (lib "easyedapro") (part "AO3400A_C5224194"))
    )
    (comp (ref "U14")
      (value "{ManufacturerPart!}")
      (footprint "easyedapro:SOP-8_L4.9-W3.9-P1.27-LS6.0-BL")
      (description "CMOS低功耗双路运算放大器")
      (fields (field (name "Manufacturer Part") "LMV358ARZ") (field (name "Manufacturer") "HTCSEMI(海天芯)"))
      (libsource (lib "easyedapro") (part "LMV358ARZ"))
    )
    (comp (ref "U15")
      (value "{ManufacturerPart!}")
      (footprint "easyedapro:SOP-8_L4.9-W3.9-P1.27-LS6.0-BL")
      (description "CMOS低功耗双路运算放大器")
      (fields (field (name "Manufacturer Part") "LMV358ARZ") (field (name "Manufacturer") "HTCSEMI(海天芯)"))
      (libsource (lib "easyedapro") (part "LMV358ARZ"))
    )
    (comp (ref "U16")
      (value "{ManufacturerPart!}")
      (footprint "easyedapro:SOP-8_L4.9-W3.9-P1.27-LS6.0-BL")
      (description "CMOS低功耗双路运算放大器")
      (fields (field (name "Manufacturer Part") "LMV358ARZ") (field (name "Manufacturer") "HTCSEMI(海天芯)"))
      (libsource (lib "easyedapro") (part "LMV358ARZ"))
    )
    (comp (ref "USB1")
      (value "TYPE-C16PIN2MD(073)")
      (footprint "easyedapro:USB-C-SMD_TYPE-C-6PIN-2MD-073")
      (description "连接器类型:Type-C;标准:-;公母:母座;触点数量:16;端口数量:1;安装方式:卧贴;额定电流 - 电源:5A;工作温度范围:-25°C~+85°C;")
      (fields (field (name "Manufacturer") "SHOU HAN(首韩)"))
      (libsource (lib "easyedapro") (part "TYPE-C 16PIN 2MD(073)"))
    )
  )
  (nets
    (net (code "1") (name "+3.3V") (class "Default")
      (node (ref "C10") (pin "1") (pinfunction "1_1") (pintype "unspecified"))
      (node (ref "C12") (pin "2") (pinfunction "2_2") (pintype "unspecified"))
      (node (ref "C16") (pin "2") (pinfunction "2_2") (pintype "unspecified"))
      (node (ref "C18") (pin "2") (pinfunction "2_2") (pintype "unspecified"))
      (node (ref "C23") (pin "1") (pinfunction "1_1") (pintype "unspecified"))
      (node (ref "C25") (pin "2") (pinfunction "2_2") (pintype "unspecified"))
      (node (ref "C30") (pin "1") (pinfunction "1_1") (pintype "input"))
      (node (ref "C31") (pin "1") (pinfunction "1_1") (pintype "input"))
      (node (ref "C32") (pin "1") (pinfunction "1_1") (pintype "input"))
      (node (ref "C33") (pin "1") (pinfunction "1_1") (pintype "input"))
      (node (ref "FPC1") (pin "5") (pinfunction "5_5") (pintype "input"))
      (node (ref "R1") (pin "2") (pinfunction "2_2") (pintype "input"))
      (node (ref "U1") (pin "5") (pinfunction "VCC_5") (pintype "unspecified"))
      (node (ref "U10") (pin "2") (pinfunction "VOUT_2") (pintype "input"))
      (node (ref "U14") (pin "8") (pinfunction "VCC_8") (pintype "input"))
      (node (ref "U15") (pin "8") (pinfunction "VCC_8") (pintype "input"))
      (node (ref "U16") (pin "8") (pinfunction "VCC_8") (pintype "input"))
      (node (ref "U2") (pin "5") (pinfunction "VCC_5") (pintype "unspecified"))
      (node (ref "U3") (pin "5") (pinfunction "VCC_5") (pintype "unspecified"))
      (node (ref "U5") (pin "17") (pinfunction "17_17") (pintype "unspecified"))
      (node (ref "U5") (pin "18") (pinfunction "18_18") (pintype "unspecified"))
      (node (ref "U6") (pin "8") (pinfunction "+VS_8") (pintype "unspecified"))
      (node (ref "U7") (pin "5") (pinfunction "VCC_5") (pintype "unspecified"))
      (node (ref "U8") (pin "5") (pinfunction "VCC_5") (pintype "unspecified"))
    )
    (net (code "2") (name "/BT+") (class "Default")
      (node (ref "BT1") (pin "2") (pinfunction "2_2") (pintype "input"))
      (node (ref "C22") (pin "2") (pinfunction "2_2") (pintype "unspecified"))
      (node (ref "R49") (pin "2") (pinfunction "2_2") (pintype "input"))
      (node (ref "SW4") (pin "1") (pinfunction "1_1") (pintype "input"))
      (node (ref "U9") (pin "5") (pinfunction "BAT_5") (pintype "input"))
    )
    (net (code "3") (name "/BT-") (class "Default")
      (node (ref "BT1") (pin "1") (pinfunction "1_1") (pintype "input"))
      (node (ref "C26") (pin "1") (pinfunction "1_1") (pintype "unspecified"))
      (node (ref "U11") (pin "6") (pinfunction "GND_6") (pintype "input"))
      (node (ref "U12") (pin "2") (pinfunction "S_2") (pintype "input"))
    )
    (net (code "4") (name "/PA3_SPI_CS_LCD_A0") (class "Default")
      (node (ref "FPC1") (pin "8") (pinfunction "8_8") (pintype "input"))
      (node (ref "U4") (pin "7") (pinfunction "7_7") (pintype "unspecified"))
    )
    (net (code "5") (name "/PA4_LCD_RST") (class "Default")
      (node (ref "FPC1") (pin "9") (pinfunction "9_9") (pintype "input"))
      (node (ref "U4") (pin "8") (pinfunction "8_8") (pintype "unspecified"))
    )
    (net (code "6") (name "/PA5_SPI_MOSI") (class "Default")
      (node (ref "FPC1") (pin "6") (pinfunction "6_6") (pintype "input"))
      (node (ref "U4") (pin "9") (pinfunction "9_9") (pintype "unspecified"))
    )
    (net (code "7") (name "/PA6_SPI_SCK") (class "Default")
      (node (ref "FPC1") (pin "7") (pinfunction "7_7") (pintype "input"))
      (node (ref "U4") (pin "10") (pinfunction "10_10") (pintype "unspecified"))
    )
    (net (code "8") (name "/PA13_10KHZPWM") (class "Default")
      (node (ref "R7") (pin "1") (pinfunction "1_1") (pintype "input"))
      (node (ref "U5") (pin "16") (pinfunction "16_16") (pintype "unspecified"))
    )
    (net (code "9") (name "/PA24_10BEI_FANG_DA") (class "Default")
      (node (ref "U1") (pin "6") (pinfunction "Select_6") (pintype "unspecified"))
      (node (ref "U5") (pin "5") (pinfunction "5_5") (pintype "unspecified"))
    )
    (net (code "10") (name "/PA25_TONG_DAO_QIE_HUAN") (class "Default")
      (node (ref "U2") (pin "6") (pinfunction "Select_6") (pintype "unspecified"))
      (node (ref "U3") (pin "6") (pinfunction "Select_6") (pintype "unspecified"))
      (node (ref "U5") (pin "4") (pinfunction "4_4") (pintype "unspecified"))
    )
    (net (code "11") (name "/PA26_LIANG_CHENG_QIE_HUAN") (class "Default")
      (node (ref "U5") (pin "3") (pinfunction "3_3") (pintype "unspecified"))
      (node (ref "U7") (pin "6") (pinfunction "Select_6") (pintype "unspecified"))
      (node (ref "U8") (pin "6") (pinfunction "Select_6") (pintype "unspecified"))
    )
    (net (code "12") (name "/PA27_ADC_A0") (class "Default")
      (node (ref "C15") (pin "2") (pinfunction "2_2") (pintype "unspecified"))
      (node (ref "R25") (pin "1") (pinfunction "1_1") (pintype "input"))
      (node (ref "U5") (pin "2") (pinfunction "2_2") (pintype "unspecified"))
    )
    (net (code "13") (name "1.65V") (class "Default")
      (node (ref "C11") (pin "1") (pinfunction "1_1") (pintype "unspecified"))
      (node (ref "C20") (pin "1") (pinfunction "1_1") (pintype "unspecified"))
      (node (ref "R11") (pin "1") (pinfunction "1_1") (pintype "input"))
      (node (ref "R14") (pin "1") (pinfunction "1_1") (pintype "input"))
      (node (ref "U6") (pin "3") (pinfunction "+IN1_3") (pintype "unspecified"))
      (node (ref "U6") (pin "5") (pinfunction "+IN2_5") (pintype "unspecified"))
    )
    (net (code "14") (name "GND") (class "Default")
      (node (ref "C1") (pin "2") (pinfunction "2_2") (pintype "input"))
      (node (ref "C10") (pin "2") (pinfunction "2_2") (pintype "unspecified"))
      (node (ref "C11") (pin "2") (pinfunction "2_2") (pintype "unspecified"))
      (node (ref "C12") (pin "1") (pinfunction "1_1") (pintype "unspecified"))
      (node (ref "C13") (pin "2") (pinfunction "2_2") (pintype "unspecified"))
      (node (ref "C15") (pin "1") (pinfunction "1_1") (pintype "unspecified"))
      (node (ref "C16") (pin "1") (pinfunction "1_1") (pintype "unspecified"))
      (node (ref "C18") (pin "1") (pinfunction "1_1") (pintype "unspecified"))
      (node (ref "C2") (pin "2") (pinfunction "2_2") (pintype "input"))
      (node (ref "C20") (pin "2") (pinfunction "2_2") (pintype "unspecified"))
      (node (ref "C21") (pin "1") (pinfunction "1_1") (pintype "unspecified"))
      (node (ref "C22") (pin "1") (pinfunction "1_1") (pintype "unspecified"))
      (node (ref "C23") (pin "2") (pinfunction "2_2") (pintype "unspecified"))
      (node (ref "C24") (pin "1") (pinfunction "1_1") (pintype "unspecified"))
      (node (ref "C25") (pin "1") (pinfunction "1_1") (pintype "unspecified"))
      (node (ref "C28") (pin "2") (pinfunction "2_2") (pintype "unspecified"))
      (node (ref "C29") (pin "2") (pinfunction "2_2") (pintype "unspecified"))
      (node (ref "C3") (pin "2") (pinfunction "2_2") (pintype "input"))
      (node (ref "C30") (pin "2") (pinfunction "2_2") (pintype "input"))
      (node (ref "C31") (pin "2") (pinfunction "2_2") (pintype "input"))
      (node (ref "C32") (pin "2") (pinfunction "2_2") (pintype "input"))
      (node (ref "C33") (pin "2") (pinfunction "2_2") (pintype "input"))
      (node (ref "C4") (pin "2") (pinfunction "2_2") (pintype "input"))
      (node (ref "C6") (pin "1") (pinfunction "1_1") (pintype "input"))
      (node (ref "C7") (pin "1") (pinfunction "1_1") (pintype "input"))
      (node (ref "C8") (pin "1") (pinfunction "1_1") (pintype "input"))
      (node (ref "C9") (pin "1") (pinfunction "1_1") (pintype "input"))
      (node (ref "FPC1") (pin "10") (pinfunction "10_10") (pintype "input"))
      (node (ref "FPC1") (pin "11") (pinfunction "11_11") (pintype "input"))
      (node (ref "FPC1") (pin "12") (pinfunction "12_12") (pintype "input"))
      (node (ref "FPC1") (pin "4") (pinfunction "4_4") (pintype "input"))
      (node (ref "R44") (pin "2") (pinfunction "2_2") (pintype "input"))
      (node (ref "R45") (pin "2") (pinfunction "2_2") (pintype "input"))
      (node (ref "R47") (pin "2") (pinfunction "2_2") (pintype "input"))
      (node (ref "R48") (pin "2") (pinfunction "2_2") (pintype "input"))
      (node (ref "R50") (pin "1") (pinfunction "1_1") (pintype "input"))
      (node (ref "R8") (pin "1") (pinfunction "1_1") (pintype "input"))
      (node (ref "RF1") (pin "1") (pinfunction "1_1") (pintype "unspecified"))
      (node (ref "RF1") (pin "2") (pinfunction "2_2") (pintype "unspecified"))
      (node (ref "RF1") (pin "3") (pinfunction "3_3") (pintype "unspecified"))
      (node (ref "RF1") (pin "4") (pinfunction "4_4") (pintype "unspecified"))
      (node (ref "RF2") (pin "1") (pinfunction "1_1") (pintype "unspecified"))
      (node (ref "RF2") (pin "2") (pinfunction "2_2") (pintype "unspecified"))
      (node (ref "RF2") (pin "3") (pinfunction "3_3") (pintype "unspecified"))
      (node (ref "RF2") (pin "4") (pinfunction "4_4") (pintype "unspecified"))
      (node (ref "RF3") (pin "1") (pinfunction "1_1") (pintype "unspecified"))
      (node (ref "RF3") (pin "2") (pinfunction "2_2") (pintype "unspecified"))
      (node (ref "RF3") (pin "3") (pinfunction "3_3") (pintype "unspecified"))
      (node (ref "RF3") (pin "4") (pinfunction "4_4") (pintype "unspecified"))
      (node (ref "RF4") (pin "1") (pinfunction "1_1") (pintype "unspecified"))
      (node (ref "RF4") (pin "2") (pinfunction "2_2") (pintype "unspecified"))
      (node (ref "RF4") (pin "3") (pinfunction "3_3") (pintype "unspecified"))
      (node (ref "RF4") (pin "4") (pinfunction "4_4") (pintype "unspecified"))
      (node (ref "SW5") (pin "3") (pinfunction "3_3") (pintype "input"))
      (node (ref "SW5") (pin "4") (pinfunction "4_4") (pintype "input"))
      (node (ref "SW6") (pin "3") (pinfunction "3_3") (pintype "input"))
      (node (ref "SW6") (pin "4") (pinfunction "4_4") (pintype "input"))
      (node (ref "SW7") (pin "3") (pinfunction "3_3") (pintype "input"))
      (node (ref "SW7") (pin "4") (pinfunction "4_4") (pintype "input"))
      (node (ref "U1") (pin "2") (pinfunction "GND_2") (pintype "unspecified"))
      (node (ref "U10") (pin "1") (pinfunction "VSS_1") (pintype "input"))
      (node (ref "U13") (pin "2") (pinfunction "S_2") (pintype "input"))
      (node (ref "U14") (pin "4") (pinfunction "GND_4") (pintype "input"))
      (node (ref "U15") (pin "4") (pinfunction "GND_4") (pintype "input"))
      (node (ref "U16") (pin "4") (pinfunction "GND_4") (pintype "input"))
      (node (ref "U2") (pin "2") (pinfunction "GND_2") (pintype "unspecified"))
      (node (ref "U3") (pin "2") (pinfunction "GND_2") (pintype "unspecified"))
      (node (ref "U4") (pin "1") (pinfunction "1_1") (pintype "unspecified"))
      (node (ref "U4") (pin "19") (pinfunction "19_19") (pintype "unspecified"))
      (node (ref "U4") (pin "20") (pinfunction "20_20") (pintype "unspecified"))
      (node (ref "U5") (pin "19") (pinfunction "19_19") (pintype "unspecified"))
      (node (ref "U5") (pin "20") (pinfunction "20_20") (pintype "unspecified"))
      (node (ref "U6") (pin "4") (pinfunction "-VS_4") (pintype "unspecified"))
      (node (ref "U7") (pin "2") (pinfunction "GND_2") (pintype "unspecified"))
      (node (ref "U8") (pin "2") (pinfunction "GND_2") (pintype "unspecified"))
      (node (ref "U9") (pin "1") (pinfunction "TEMP_1") (pintype "input"))
      (node (ref "U9") (pin "3") (pinfunction "GND_3") (pintype "input"))
      (node (ref "USB1") (pin "1") (pinfunction "GND_1") (pintype "input"))
      (node (ref "USB1") (pin "12") (pinfunction "GND_12") (pintype "input"))
      (node (ref "USB1") (pin "13") (pinfunction "SHELL_13") (pintype "input"))
      (node (ref "USB1") (pin "14") (pinfunction "SHELL_14") (pintype "input"))
    )
    (net (code "15") (name "Net-(C1-Pad1)") (class "Default")
      (node (ref "C1") (pin "1") (pinfunction "1_1") (pintype "input"))
      (node (ref "C5") (pin "2") (pinfunction "2_2") (pintype "input"))
      (node (ref "C6") (pin "2") (pinfunction "2_2") (pintype "input"))
      (node (ref "R2") (pin "1") (pinfunction "1_1") (pintype "input"))
    )
    (net (code "16") (name "Net-(C2-Pad1)") (class "Default")
      (node (ref "C2") (pin "1") (pinfunction "1_1") (pintype "input"))
      (node (ref "C7") (pin "2") (pinfunction "2_2") (pintype "input"))
      (node (ref "R2") (pin "2") (pinfunction "2_2") (pintype "input"))
      (node (ref "R3") (pin "1") (pinfunction "1_1") (pintype "input"))
    )
    (net (code "17") (name "Net-(C3-Pad1)") (class "Default")
      (node (ref "C3") (pin "1") (pinfunction "1_1") (pintype "input"))
      (node (ref "C8") (pin "2") (pinfunction "2_2") (pintype "input"))
      (node (ref "R3") (pin "2") (pinfunction "2_2") (pintype "input"))
      (node (ref "R4") (pin "1") (pinfunction "1_1") (pintype "input"))
    )
    (net (code "18") (name "Net-(C4-Pad1)") (class "Default")
      (node (ref "C4") (pin "1") (pinfunction "1_1") (pintype "input"))
      (node (ref "C9") (pin "2") (pinfunction "2_2") (pintype "input"))
      (node (ref "R4") (pin "2") (pinfunction "2_2") (pintype "input"))
      (node (ref "R5") (pin "1") (pinfunction "1_1") (pintype "input"))
    )
    (net (code "19") (name "Net-(C13-Pad1)") (class "Default")
      (node (ref "C13") (pin "1") (pinfunction "1_1") (pintype "unspecified"))
      (node (ref "R17") (pin "1") (pinfunction "1_1") (pintype "input"))
      (node (ref "R19") (pin "2") (pinfunction "2_2") (pintype "input"))
    )
    (net (code "20") (name "Net-(C27-Pad1)") (class "Default")
      (node (ref "C27") (pin "1") (pinfunction "1_1") (pintype "unspecified"))
      (node (ref "FPC1") (pin "3") (pinfunction "3_3") (pintype "input"))
    )
    (net (code "21") (name "Net-(C27-Pad2)") (class "Default")
      (node (ref "C27") (pin "2") (pinfunction "2_2") (pintype "unspecified"))
      (node (ref "FPC1") (pin "2") (pinfunction "2_2") (pintype "input"))
    )
    (net (code "22") (name "Net-(C28-Pad1)") (class "Default")
      (node (ref "C28") (pin "1") (pinfunction "1_1") (pintype "unspecified"))
      (node (ref "FPC1") (pin "1") (pinfunction "1_1") (pintype "input"))
    )
    (net (code "23") (name "Net-(C29-Pad1)") (class "Default")
      (node (ref "C29") (pin "1") (pinfunction "1_1") (pintype "unspecified"))
      (node (ref "R21") (pin "1") (pinfunction "1_1") (pintype "input"))
      (node (ref "R26") (pin "2") (pinfunction "2_2") (pintype "input"))
    )
    (net (code "24") (name "Net-(LED1-A)") (class "Default")
      (node (ref "C21") (pin "2") (pinfunction "2_2") (pintype "unspecified"))
      (node (ref "LED1") (pin "1") (pinfunction "A_1") (pintype "input"))
      (node (ref "LED2") (pin "1") (pinfunction "A_1") (pintype "input"))
      (node (ref "U9") (pin "4") (pinfunction "Vcc_4") (pintype "input"))
      (node (ref "U9") (pin "8") (pinfunction "CE_8") (pintype "input"))
      (node (ref "USB1") (pin "11") (pinfunction "VBUS_11") (pintype "input"))
      (node (ref "USB1") (pin "2") (pinfunction "VBUS_2") (pintype "input"))
    )
    (net (code "25") (name "Net-(LED1-K)") (class "Default")
      (node (ref "LED1") (pin "2") (pinfunction "K_2") (pintype "input"))
      (node (ref "R42") (pin "2") (pinfunction "2_2") (pintype "input"))
    )
    (net (code "26") (name "Net-(LED2-K)") (class "Default")
      (node (ref "LED2") (pin "2") (pinfunction "K_2") (pintype "input"))
      (node (ref "R43") (pin "2") (pinfunction "2_2") (pintype "input"))
    )
    (net (code "27") (name "Net-(R5-Pad2)") (class "Default")
      (node (ref "R5") (pin "2") (pinfunction "2_2") (pintype "input"))
      (node (ref "R6") (pin "2") (pinfunction "2_2") (pintype "input"))
    )
    (net (code "28") (name "Net-(R6-Pad1)") (class "Default")
      (node (ref "R6") (pin "1") (pinfunction "1_1") (pintype "input"))
      (node (ref "R7") (pin "2") (pinfunction "2_2") (pintype "input"))
    )
    (net (code "29") (name "Net-(R12-Pad2)") (class "Default")
      (node (ref "R12") (pin "2") (pinfunction "2_2") (pintype "input"))
      (node (ref "R22") (pin "1") (pinfunction "1_1") (pintype "input"))
      (node (ref "R9") (pin "2") (pinfunction "2_2") (pintype "input"))
      (node (ref "RF1") (pin "5") (pinfunction "5_5") (pintype "unspecified"))
    )
    (net (code "30") (name "Net-(R20-Pad2)") (class "Default")
      (node (ref "R20") (pin "2") (pinfunction "2_2") (pintype "input"))
      (node (ref "R22") (pin "2") (pinfunction "2_2") (pintype "input"))
      (node (ref "RF2") (pin "5") (pinfunction "5_5") (pintype "unspecified"))
    )
    (net (code "31") (name "Net-(R28-Pad2)") (class "Default")
      (node (ref "R28") (pin "2") (pinfunction "2_2") (pintype "input"))
      (node (ref "R32") (pin "1") (pinfunction "1_1") (pintype "input"))
      (node (ref "RF3") (pin "5") (pinfunction "5_5") (pintype "unspecified"))
    )
    (net (code "32") (name "Net-(R36-Pad1)") (class "Default")
      (node (ref "R36") (pin "1") (pinfunction "1_1") (pintype "input"))
      (node (ref "SW5") (pin "1") (pinfunction "1_1") (pintype "input"))
      (node (ref "SW5") (pin "2") (pinfunction "2_2") (pintype "input"))
    )
    (net (code "33") (name "Net-(R36-Pad2)") (class "Default")
      (node (ref "R36") (pin "2") (pinfunction "2_2") (pintype "input"))
      (node (ref "U4") (pin "14") (pinfunction "14_14") (pintype "unspecified"))
    )
    (net (code "34") (name "Net-(R37-Pad1)") (class "Default")
      (node (ref "R37") (pin "1") (pinfunction "1_1") (pintype "input"))
      (node (ref "SW6") (pin "1") (pinfunction "1_1") (pintype "input"))
      (node (ref "SW6") (pin "2") (pinfunction "2_2") (pintype "input"))
    )
    (net (code "35") (name "Net-(R37-Pad2)") (class "Default")
      (node (ref "R37") (pin "2") (pinfunction "2_2") (pintype "input"))
      (node (ref "U4") (pin "15") (pinfunction "15_15") (pintype "unspecified"))
    )
    (net (code "36") (name "Net-(R38-Pad1)") (class "Default")
      (node (ref "R38") (pin "1") (pinfunction "1_1") (pintype "input"))
      (node (ref "SW7") (pin "1") (pinfunction "1_1") (pintype "input"))
      (node (ref "SW7") (pin "2") (pinfunction "2_2") (pintype "input"))
    )
    (net (code "37") (name "Net-(R38-Pad2)") (class "Default")
      (node (ref "R38") (pin "2") (pinfunction "2_2") (pintype "input"))
      (node (ref "U4") (pin "16") (pinfunction "16_16") (pintype "unspecified"))
    )
    (net (code "38") (name "Net-(R45-Pad1)") (class "Default")
      (node (ref "R45") (pin "1") (pinfunction "1_1") (pintype "input"))
      (node (ref "R46") (pin "2") (pinfunction "2_2") (pintype "input"))
      (node (ref "R48") (pin "1") (pinfunction "1_1") (pintype "input"))
    )
    (net (code "39") (name "Net-(U1-A)") (class "Default")
      (node (ref "R23") (pin "1") (pinfunction "1_1") (pintype "input"))
      (node (ref "U1") (pin "4") (pinfunction "A_4") (pintype "unspecified"))
    )
    (net (code "40") (name "Net-(U1-B0)") (class "Default")
      (node (ref "R15") (pin "1") (pinfunction "1_1") (pintype "input"))
      (node (ref "R16") (pin "1") (pinfunction "1_1") (pintype "input"))
      (node (ref "R17") (pin "2") (pinfunction "2_2") (pintype "input"))
      (node (ref "U1") (pin "3") (pinfunction "B0_3") (pintype "unspecified"))
    )
    (net (code "41") (name "Net-(U1-B1)") (class "Default")
      (node (ref "R15") (pin "2") (pinfunction "2_2") (pintype "input"))
      (node (ref "R16") (pin "2") (pinfunction "2_2") (pintype "input"))
      (node (ref "R30") (pin "2") (pinfunction "2_2") (pintype "input"))
      (node (ref "U1") (pin "1") (pinfunction "B1_1") (pintype "unspecified"))
      (node (ref "U15") (pin "1") (pinfunction "OUT_1") (pintype "output"))
    )
    (net (code "42") (name "Net-(U2-B0)") (class "Default")
      (node (ref "R24") (pin "1") (pinfunction "1_1") (pintype "input"))
      (node (ref "U2") (pin "3") (pinfunction "B0_3") (pintype "unspecified"))
    )
    (net (code "43") (name "Net-(U2-B1)") (class "Default")
      (node (ref "R20") (pin "1") (pinfunction "1_1") (pintype "input"))
      (node (ref "U2") (pin "1") (pinfunction "B1_1") (pintype "unspecified"))
    )
    (net (code "44") (name "Net-(U3-B0)") (class "Default")
      (node (ref "R31") (pin "1") (pinfunction "1_1") (pintype "input"))
      (node (ref "U3") (pin "3") (pinfunction "B0_3") (pintype "unspecified"))
    )
    (net (code "45") (name "Net-(U3-B1)") (class "Default")
      (node (ref "R28") (pin "1") (pinfunction "1_1") (pintype "input"))
      (node (ref "U3") (pin "1") (pinfunction "B1_1") (pintype "unspecified"))
    )
    (net (code "46") (name "Net-(U6--IN1)") (class "Default")
      (node (ref "C19") (pin "2") (pinfunction "2_2") (pintype "input"))
      (node (ref "R31") (pin "2") (pinfunction "2_2") (pintype "input"))
      (node (ref "R32") (pin "2") (pinfunction "2_2") (pintype "input"))
      (node (ref "R34") (pin "2") (pinfunction "2_2") (pintype "input"))
      (node (ref "R35") (pin "2") (pinfunction "2_2") (pintype "input"))
      (node (ref "R40") (pin "2") (pinfunction "2_2") (pintype "input"))
      (node (ref "R41") (pin "2") (pinfunction "2_2") (pintype "input"))
      (node (ref "RF4") (pin "5") (pinfunction "5_5") (pintype "unspecified"))
      (node (ref "U6") (pin "2") (pinfunction "-IN1_2") (pintype "unspecified"))
      (node (ref "U6") (pin "6") (pinfunction "-IN2_6") (pintype "unspecified"))
    )
    (net (code "47") (name "Net-(U6-OUTA)") (class "Default")
      (node (ref "R39") (pin "1") (pinfunction "1_1") (pintype "unspecified"))
      (node (ref "U6") (pin "1") (pinfunction "OUTA_1") (pintype "unspecified"))
    )
    (net (code "48") (name "Net-(U6-OUTB)") (class "Default")
      (node (ref "R33") (pin "1") (pinfunction "1_1") (pintype "unspecified"))
      (node (ref "U6") (pin "7") (pinfunction "OUTB_7") (pintype "unspecified"))
    )
    (net (code "49") (name "Net-(U7-A)") (class "Default")
      (node (ref "R33") (pin "2") (pinfunction "2_2") (pintype "unspecified"))
      (node (ref "R39") (pin "2") (pinfunction "2_2") (pintype "unspecified"))
      (node (ref "U7") (pin "4") (pinfunction "A_4") (pintype "unspecified"))
    )
    (net (code "50") (name "Net-(U7-B0)") (class "Default")
      (node (ref "R40") (pin "1") (pinfunction "1_1") (pintype "input"))
      (node (ref "R41") (pin "1") (pinfunction "1_1") (pintype "input"))
      (node (ref "U7") (pin "3") (pinfunction "B0_3") (pintype "unspecified"))
      (node (ref "U8") (pin "3") (pinfunction "B0_3") (pintype "unspecified"))
    )
    (net (code "51") (name "Net-(U7-B1)") (class "Default")
      (node (ref "C19") (pin "1") (pinfunction "1_1") (pintype "input"))
      (node (ref "R34") (pin "1") (pinfunction "1_1") (pintype "input"))
      (node (ref "R35") (pin "1") (pinfunction "1_1") (pintype "input"))
      (node (ref "U7") (pin "1") (pinfunction "B1_1") (pintype "unspecified"))
      (node (ref "U8") (pin "1") (pinfunction "B1_1") (pintype "unspecified"))
    )
    (net (code "52") (name "Net-(U8-A)") (class "Default")
      (node (ref "R24") (pin "2") (pinfunction "2_2") (pintype "input"))
      (node (ref "U8") (pin "4") (pinfunction "A_4") (pintype "unspecified"))
    )
    (net (code "53") (name "Net-(U9-CHRG#)") (class "Default")
      (node (ref "R42") (pin "1") (pinfunction "1_1") (pintype "input"))
      (node (ref "U9") (pin "7") (pinfunction "CHRG#_7") (pintype "input"))
    )
    (net (code "54") (name "Net-(U9-PROG)") (class "Default")
      (node (ref "R46") (pin "1") (pinfunction "1_1") (pintype "input"))
      (node (ref "U9") (pin "2") (pinfunction "PROG_2") (pintype "input"))
    )
    (net (code "55") (name "Net-(U9-STDBY#)") (class "Default")
      (node (ref "R43") (pin "1") (pinfunction "1_1") (pintype "input"))
      (node (ref "U9") (pin "6") (pinfunction "STDBY#_6") (pintype "input"))
    )
    (net (code "56") (name "Net-(U11-CS)") (class "Default")
      (node (ref "R50") (pin "2") (pinfunction "2_2") (pintype "input"))
      (node (ref "U11") (pin "2") (pinfunction "CS_2") (pintype "input"))
    )
    (net (code "57") (name "Net-(U11-OC)") (class "Default")
      (node (ref "U11") (pin "3") (pinfunction "OC_3") (pintype "input"))
      (node (ref "U13") (pin "1") (pinfunction "G_1") (pintype "input"))
    )
    (net (code "58") (name "Net-(U11-OD)") (class "Default")
      (node (ref "U11") (pin "1") (pinfunction "OD_1") (pintype "input"))
      (node (ref "U12") (pin "1") (pinfunction "G_1") (pintype "input"))
    )
    (net (code "59") (name "Net-(U11-VCC)") (class "Default")
      (node (ref "C26") (pin "2") (pinfunction "2_2") (pintype "unspecified"))
      (node (ref "R49") (pin "1") (pinfunction "1_1") (pintype "input"))
      (node (ref "U11") (pin "5") (pinfunction "VCC_5") (pintype "input"))
    )
    (net (code "60") (name "Net-(U12-D)") (class "Default")
      (node (ref "U12") (pin "3") (pinfunction "D_3") (pintype "input"))
      (node (ref "U13") (pin "3") (pinfunction "D_3") (pintype "input"))
    )
    (net (code "61") (name "Net-(U14A-IN1+)") (class "Default")
      (node (ref "U14") (pin "3") (pinfunction "IN1+_3") (pintype "input"))
      (node (ref "U2") (pin "4") (pinfunction "A_4") (pintype "unspecified"))
    )
    (net (code "62") (name "Net-(U14A-IN1-)") (class "Default")
      (node (ref "R18") (pin "1") (pinfunction "1_1") (pintype "input"))
      (node (ref "U14") (pin "1") (pinfunction "OUT_1") (pintype "output"))
      (node (ref "U14") (pin "2") (pinfunction "IN1-_2") (pintype "input"))
    )
    (net (code "63") (name "Net-(U14B-IN2+)") (class "Default")
      (node (ref "U14") (pin "5") (pinfunction "IN2+_5") (pintype "input"))
      (node (ref "U3") (pin "4") (pinfunction "A_4") (pintype "unspecified"))
    )
    (net (code "64") (name "Net-(U14B-IN2-)") (class "Default")
      (node (ref "R29") (pin "1") (pinfunction "1_1") (pintype "input"))
      (node (ref "U14") (pin "6") (pinfunction "IN2-_6") (pintype "input"))
      (node (ref "U14") (pin "7") (pinfunction "OUT2_7") (pintype "output"))
    )
    (net (code "65") (name "Net-(U15A-IN1+)") (class "Default")
      (node (ref "R18") (pin "2") (pinfunction "2_2") (pintype "input"))
      (node (ref "R19") (pin "1") (pinfunction "1_1") (pintype "input"))
      (node (ref "U15") (pin "3") (pinfunction "IN1+_3") (pintype "input"))
    )
    (net (code "66") (name "Net-(U15A-IN1-)") (class "Default")
      (node (ref "R29") (pin "2") (pinfunction "2_2") (pintype "input"))
      (node (ref "R30") (pin "1") (pinfunction "1_1") (pintype "input"))
      (node (ref "U15") (pin "2") (pinfunction "IN1-_2") (pintype "input"))
    )
    (net (code "67") (name "Net-(U15B-IN2+)") (class "Default")
      (node (ref "R21") (pin "2") (pinfunction "2_2") (pintype "input"))
      (node (ref "R23") (pin "2") (pinfunction "2_2") (pintype "input"))
      (node (ref "U15") (pin "5") (pinfunction "IN2+_5") (pintype "input"))
    )
    (net (code "68") (name "Net-(U15B-IN2-)") (class "Default")
      (node (ref "R26") (pin "1") (pinfunction "1_1") (pintype "input"))
      (node (ref "R27") (pin "1") (pinfunction "1_1") (pintype "input"))
      (node (ref "U15") (pin "6") (pinfunction "IN2-_6") (pintype "input"))
    )
    (net (code "69") (name "Net-(U15B-OUT2)") (class "Default")
      (node (ref "R25") (pin "2") (pinfunction "2_2") (pintype "input"))
      (node (ref "R27") (pin "2") (pinfunction "2_2") (pintype "input"))
      (node (ref "U15") (pin "7") (pinfunction "OUT2_7") (pintype "output"))
    )
    (net (code "70") (name "Net-(U16A-IN1+)") (class "Default")
      (node (ref "C5") (pin "1") (pinfunction "1_1") (pintype "input"))
      (node (ref "R1") (pin "1") (pinfunction "1_1") (pintype "input"))
      (node (ref "R8") (pin "2") (pinfunction "2_2") (pintype "input"))
      (node (ref "TP1") (pin "1") (pinfunction "1_1") (pintype "input"))
      (node (ref "U16") (pin "3") (pinfunction "IN1+_3") (pintype "input"))
      (node (ref "U16") (pin "5") (pinfunction "IN2+_5") (pintype "input"))
    )
    (net (code "71") (name "Net-(U16A-IN1-)") (class "Default")
      (node (ref "R10") (pin "2") (pinfunction "2_2") (pintype "unspecified"))
      (node (ref "R11") (pin "2") (pinfunction "2_2") (pintype "input"))
      (node (ref "U16") (pin "2") (pinfunction "IN1-_2") (pintype "input"))
    )
    (net (code "72") (name "Net-(U16A-OUT)") (class "Default")
      (node (ref "R10") (pin "1") (pinfunction "1_1") (pintype "unspecified"))
      (node (ref "R9") (pin "1") (pinfunction "1_1") (pintype "input"))
      (node (ref "U16") (pin "1") (pinfunction "OUT_1") (pintype "output"))
    )
    (net (code "73") (name "Net-(U16B-IN2-)") (class "Default")
      (node (ref "R13") (pin "2") (pinfunction "2_2") (pintype "unspecified"))
      (node (ref "R14") (pin "2") (pinfunction "2_2") (pintype "input"))
      (node (ref "U16") (pin "6") (pinfunction "IN2-_6") (pintype "input"))
    )
    (net (code "74") (name "Net-(U16B-OUT2)") (class "Default")
      (node (ref "R12") (pin "1") (pinfunction "1_1") (pintype "input"))
      (node (ref "R13") (pin "1") (pinfunction "1_1") (pintype "unspecified"))
      (node (ref "U16") (pin "7") (pinfunction "OUT2_7") (pintype "output"))
    )
    (net (code "75") (name "Net-(USB1-CC1)") (class "Default")
      (node (ref "R47") (pin "1") (pinfunction "1_1") (pintype "input"))
      (node (ref "USB1") (pin "4") (pinfunction "CC1_4") (pintype "input"))
    )
    (net (code "76") (name "Net-(USB1-CC2)") (class "Default")
      (node (ref "R44") (pin "1") (pinfunction "1_1") (pintype "input"))
      (node (ref "USB1") (pin "10") (pinfunction "CC2_10") (pintype "input"))
    )
    (net (code "77") (name "VCC") (class "Default")
      (node (ref "C24") (pin "2") (pinfunction "2_2") (pintype "unspecified"))
      (node (ref "SW4") (pin "2") (pinfunction "2_2") (pintype "input"))
      (node (ref "SW4") (pin "3") (pinfunction "3_3") (pintype "input"))
      (node (ref "U10") (pin "3") (pinfunction "VIN_3") (pintype "input"))
    )
    (net (code "78") (name "unconnected-(TP2-Pad1)") (class "Default")
      (node (ref "TP2") (pin "1") (pinfunction "1_1") (pintype "input"))
    )
    (net (code "79") (name "unconnected-(U4-Pad2)") (class "Default")
      (node (ref "U4") (pin "2") (pinfunction "2_2") (pintype "unspecified"))
    )
    (net (code "80") (name "unconnected-(U4-Pad3)") (class "Default")
      (node (ref "U4") (pin "3") (pinfunction "3_3") (pintype "unspecified"))
    )
    (net (code "81") (name "unconnected-(U4-Pad4)") (class "Default")
      (node (ref "U4") (pin "4") (pinfunction "4_4") (pintype "unspecified"))
    )
    (net (code "82") (name "unconnected-(U4-Pad5)") (class "Default")
      (node (ref "U4") (pin "5") (pinfunction "5_5") (pintype "unspecified"))
    )
    (net (code "83") (name "unconnected-(U4-Pad6)") (class "Default")
      (node (ref "U4") (pin "6") (pinfunction "6_6") (pintype "unspecified"))
    )
    (net (code "84") (name "unconnected-(U4-Pad11)") (class "Default")
      (node (ref "U4") (pin "11") (pinfunction "11_11") (pintype "unspecified"))
    )
    (net (code "85") (name "unconnected-(U4-Pad12)") (class "Default")
      (node (ref "U4") (pin "12") (pinfunction "12_12") (pintype "unspecified"))
    )
    (net (code "86") (name "unconnected-(U4-Pad13)") (class "Default")
      (node (ref "U4") (pin "13") (pinfunction "13_13") (pintype "unspecified"))
    )
    (net (code "87") (name "unconnected-(U4-Pad17)") (class "Default")
      (node (ref "U4") (pin "17") (pinfunction "17_17") (pintype "unspecified"))
    )
    (net (code "88") (name "unconnected-(U4-Pad18)") (class "Default")
      (node (ref "U4") (pin "18") (pinfunction "18_18") (pintype "unspecified"))
    )
    (net (code "89") (name "unconnected-(U5-Pad1)") (class "Default")
      (node (ref "U5") (pin "1") (pinfunction "1_1") (pintype "unspecified"))
    )
    (net (code "90") (name "unconnected-(U5-Pad6)") (class "Default")
      (node (ref "U5") (pin "6") (pinfunction "6_6") (pintype "unspecified"))
    )
    (net (code "91") (name "unconnected-(U5-Pad7)") (class "Default")
      (node (ref "U5") (pin "7") (pinfunction "7_7") (pintype "unspecified"))
    )
    (net (code "92") (name "unconnected-(U5-Pad8)") (class "Default")
      (node (ref "U5") (pin "8") (pinfunction "8_8") (pintype "unspecified"))
    )
    (net (code "93") (name "unconnected-(U5-Pad9)") (class "Default")
      (node (ref "U5") (pin "9") (pinfunction "9_9") (pintype "unspecified"))
    )
    (net (code "94") (name "unconnected-(U5-Pad10)") (class "Default")
      (node (ref "U5") (pin "10") (pinfunction "10_10") (pintype "unspecified"))
    )
    (net (code "95") (name "unconnected-(U5-Pad11)") (class "Default")
      (node (ref "U5") (pin "11") (pinfunction "11_11") (pintype "unspecified"))
    )
    (net (code "96") (name "unconnected-(U5-Pad12)") (class "Default")
      (node (ref "U5") (pin "12") (pinfunction "12_12") (pintype "unspecified"))
    )
    (net (code "97") (name "unconnected-(U5-Pad13)") (class "Default")
      (node (ref "U5") (pin "13") (pinfunction "13_13") (pintype "unspecified"))
    )
    (net (code "98") (name "unconnected-(U5-Pad14)") (class "Default")
      (node (ref "U5") (pin "14") (pinfunction "14_14") (pintype "unspecified"))
    )
    (net (code "99") (name "unconnected-(U5-Pad15)") (class "Default")
      (node (ref "U5") (pin "15") (pinfunction "15_15") (pintype "unspecified"))
    )
    (net (code "100") (name "unconnected-(U11-TD-Pad4)") (class "Default")
      (node (ref "U11") (pin "4") (pinfunction "TD_4") (pintype "input"))
    )
    (net (code "101") (name "unconnected-(USB1-DN1-Pad7)") (class "Default")
      (node (ref "USB1") (pin "7") (pinfunction "DN1_7") (pintype "input"))
    )
    (net (code "102") (name "unconnected-(USB1-DN2-Pad5)") (class "Default")
      (node (ref "USB1") (pin "5") (pinfunction "DN2_5") (pintype "input"))
    )
    (net (code "103") (name "unconnected-(USB1-DP1-Pad6)") (class "Default")
      (node (ref "USB1") (pin "6") (pinfunction "DP1_6") (pintype "input"))
    )
    (net (code "104") (name "unconnected-(USB1-DP2-Pad8)") (class "Default")
      (node (ref "USB1") (pin "8") (pinfunction "DP2_8") (pintype "input"))
    )
    (net (code "105") (name "unconnected-(USB1-SBU1-Pad9)") (class "Default")
      (node (ref "USB1") (pin "9") (pinfunction "SBU1_9") (pintype "input"))
    )
    (net (code "106") (name "unconnected-(USB1-SBU2-Pad3)") (class "Default")
      (node (ref "USB1") (pin "3") (pinfunction "SBU2_3") (pintype "input"))
    )
  )
)
